# Hand.net
KiCad netlist of a schematic drawn in EAGLE
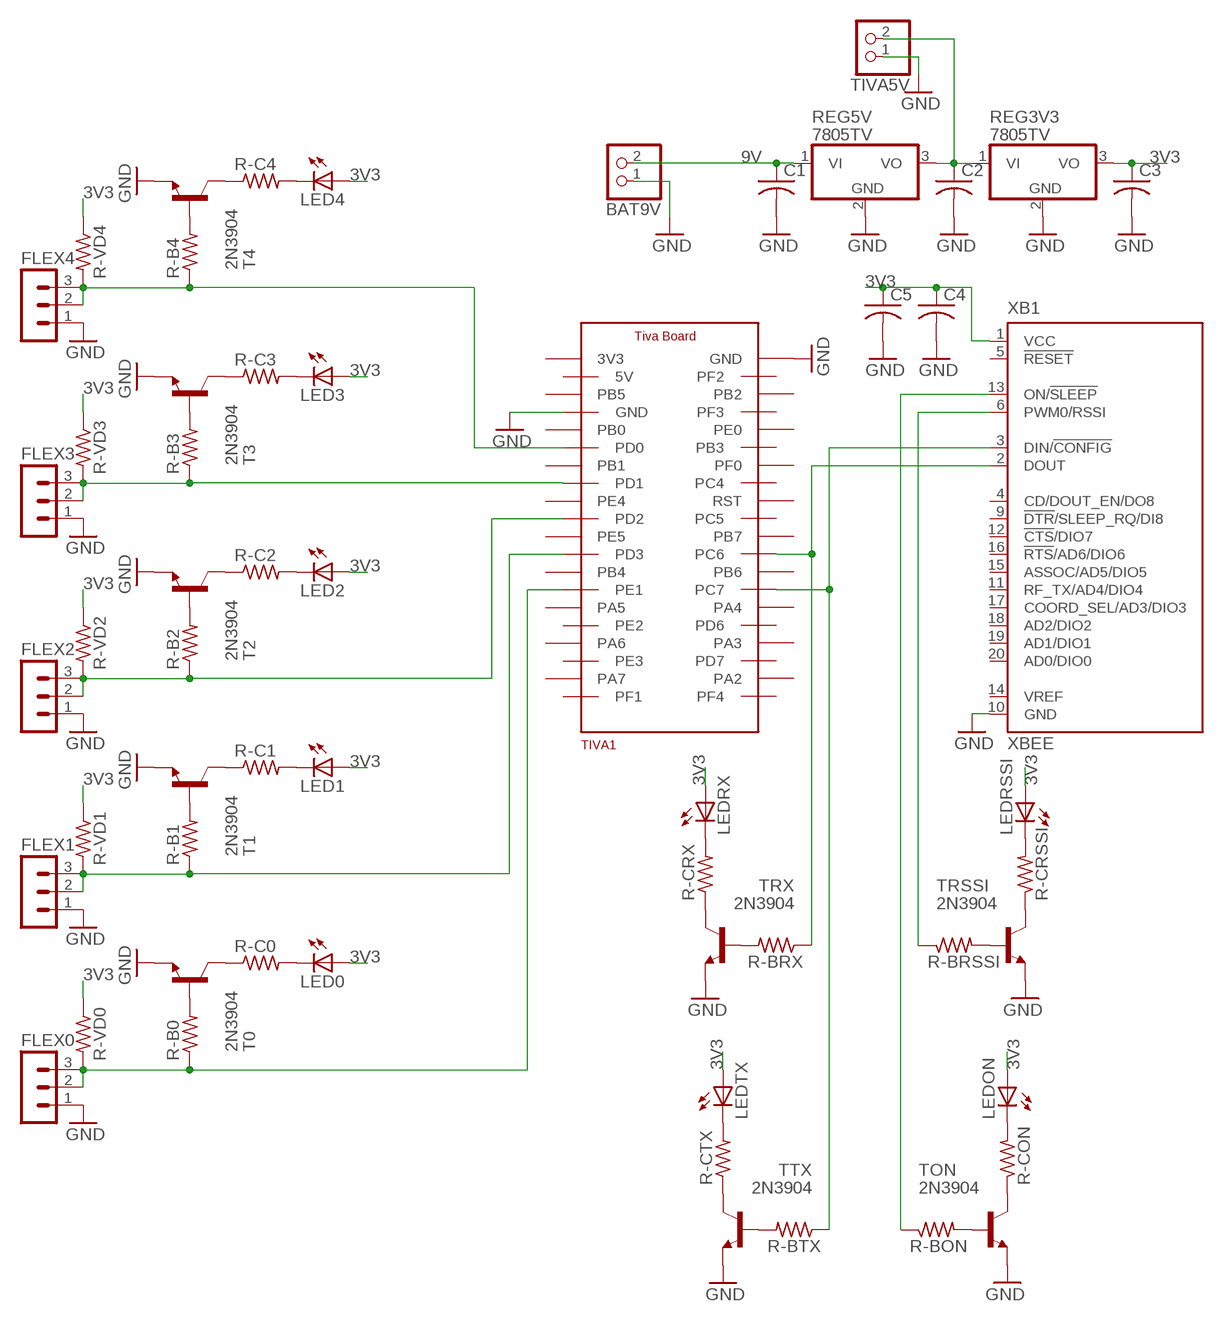
[diagram p0: schematic, sheet 1]

(export (version "E")
  (design (tool "Eeschema 10.0.6"))
  (components
    (comp (ref "BAT9V")
      (value "PINHD-1X2")
      (footprint "eagle-import:1X02")
      (libsource (lib "eagle-import") (part "PINHD-1X2"))
    )
    (comp (ref "C1")
      (value "C-US025-025X050")
      (footprint "eagle-import:C025-025X050")
      (libsource (lib "eagle-import") (part "C-US025-025X050"))
    )
    (comp (ref "C2")
      (value "C-US025-025X050")
      (footprint "eagle-import:C025-025X050")
      (libsource (lib "eagle-import") (part "C-US025-025X050"))
    )
    (comp (ref "C3")
      (value "C-US025-025X050")
      (footprint "eagle-import:C025-025X050")
      (libsource (lib "eagle-import") (part "C-US025-025X050"))
    )
    (comp (ref "C4")
      (value "C-US025-025X050")
      (footprint "eagle-import:C025-025X050")
      (libsource (lib "eagle-import") (part "C-US025-025X050"))
    )
    (comp (ref "C5")
      (value "C-US025-025X050")
      (footprint "eagle-import:C025-025X050")
      (libsource (lib "eagle-import") (part "C-US025-025X050"))
    )
    (comp (ref "FLEX0")
      (value "MA03-1")
      (footprint "eagle-import:MA03-1")
      (libsource (lib "eagle-import") (part "MA03-1"))
    )
    (comp (ref "FLEX1")
      (value "MA03-1")
      (footprint "eagle-import:MA03-1")
      (libsource (lib "eagle-import") (part "MA03-1"))
    )
    (comp (ref "FLEX2")
      (value "MA03-1")
      (footprint "eagle-import:MA03-1")
      (libsource (lib "eagle-import") (part "MA03-1"))
    )
    (comp (ref "FLEX3")
      (value "MA03-1")
      (footprint "eagle-import:MA03-1")
      (libsource (lib "eagle-import") (part "MA03-1"))
    )
    (comp (ref "FLEX4")
      (value "MA03-1")
      (footprint "eagle-import:MA03-1")
      (libsource (lib "eagle-import") (part "MA03-1"))
    )
    (comp (ref "LED0")
      (value "LED5MM")
      (footprint "eagle-import:LED5MM")
      (libsource (lib "eagle-import") (part "LED5MM"))
    )
    (comp (ref "LED1")
      (value "LED5MM")
      (footprint "eagle-import:LED5MM")
      (libsource (lib "eagle-import") (part "LED5MM"))
    )
    (comp (ref "LED2")
      (value "LED5MM")
      (footprint "eagle-import:LED5MM")
      (libsource (lib "eagle-import") (part "LED5MM"))
    )
    (comp (ref "LED3")
      (value "LED5MM")
      (footprint "eagle-import:LED5MM")
      (libsource (lib "eagle-import") (part "LED5MM"))
    )
    (comp (ref "LED4")
      (value "LED5MM")
      (footprint "eagle-import:LED5MM")
      (libsource (lib "eagle-import") (part "LED5MM"))
    )
    (comp (ref "LEDON")
      (value "LED5MM")
      (footprint "eagle-import:LED5MM")
      (libsource (lib "eagle-import") (part "LED5MM"))
    )
    (comp (ref "LEDRSSI")
      (value "LED5MM")
      (footprint "eagle-import:LED5MM")
      (libsource (lib "eagle-import") (part "LED5MM"))
    )
    (comp (ref "LEDRX")
      (value "LED5MM")
      (footprint "eagle-import:LED5MM")
      (libsource (lib "eagle-import") (part "LED5MM"))
    )
    (comp (ref "LEDTX")
      (value "LED5MM")
      (footprint "eagle-import:LED5MM")
      (libsource (lib "eagle-import") (part "LED5MM"))
    )
    (comp (ref "R-B0")
      (value "R-US_0204/7")
      (footprint "eagle-import:0204_7")
      (libsource (lib "eagle-import") (part "R-US_0204/7"))
    )
    (comp (ref "R-B1")
      (value "R-US_0204/7")
      (footprint "eagle-import:0204_7")
      (libsource (lib "eagle-import") (part "R-US_0204/7"))
    )
    (comp (ref "R-B2")
      (value "R-US_0204/7")
      (footprint "eagle-import:0204_7")
      (libsource (lib "eagle-import") (part "R-US_0204/7"))
    )
    (comp (ref "R-B3")
      (value "R-US_0204/7")
      (footprint "eagle-import:0204_7")
      (libsource (lib "eagle-import") (part "R-US_0204/7"))
    )
    (comp (ref "R-B4")
      (value "R-US_0204/7")
      (footprint "eagle-import:0204_7")
      (libsource (lib "eagle-import") (part "R-US_0204/7"))
    )
    (comp (ref "R-BON")
      (value "R-US_0204/7")
      (footprint "eagle-import:0204_7")
      (libsource (lib "eagle-import") (part "R-US_0204/7"))
    )
    (comp (ref "R-BRSSI")
      (value "R-US_0204/7")
      (footprint "eagle-import:0204_7")
      (libsource (lib "eagle-import") (part "R-US_0204/7"))
    )
    (comp (ref "R-BRX")
      (value "R-US_0204/7")
      (footprint "eagle-import:0204_7")
      (libsource (lib "eagle-import") (part "R-US_0204/7"))
    )
    (comp (ref "R-BTX")
      (value "R-US_0204/7")
      (footprint "eagle-import:0204_7")
      (libsource (lib "eagle-import") (part "R-US_0204/7"))
    )
    (comp (ref "R-C0")
      (value "R-US_0204/7")
      (footprint "eagle-import:0204_7")
      (libsource (lib "eagle-import") (part "R-US_0204/7"))
    )
    (comp (ref "R-C1")
      (value "R-US_0204/7")
      (footprint "eagle-import:0204_7")
      (libsource (lib "eagle-import") (part "R-US_0204/7"))
    )
    (comp (ref "R-C2")
      (value "R-US_0204/7")
      (footprint "eagle-import:0204_7")
      (libsource (lib "eagle-import") (part "R-US_0204/7"))
    )
    (comp (ref "R-C3")
      (value "R-US_0204/7")
      (footprint "eagle-import:0204_7")
      (libsource (lib "eagle-import") (part "R-US_0204/7"))
    )
    (comp (ref "R-C4")
      (value "R-US_0204/7")
      (footprint "eagle-import:0204_7")
      (libsource (lib "eagle-import") (part "R-US_0204/7"))
    )
    (comp (ref "R-CON")
      (value "R-US_0204/7")
      (footprint "eagle-import:0204_7")
      (libsource (lib "eagle-import") (part "R-US_0204/7"))
    )
    (comp (ref "R-CRSSI")
      (value "R-US_0204/7")
      (footprint "eagle-import:0204_7")
      (libsource (lib "eagle-import") (part "R-US_0204/7"))
    )
    (comp (ref "R-CRX")
      (value "R-US_0204/7")
      (footprint "eagle-import:0204_7")
      (libsource (lib "eagle-import") (part "R-US_0204/7"))
    )
    (comp (ref "R-CTX")
      (value "R-US_0204/7")
      (footprint "eagle-import:0204_7")
      (libsource (lib "eagle-import") (part "R-US_0204/7"))
    )
    (comp (ref "R-VD0")
      (value "R-US_0204/7")
      (footprint "eagle-import:0204_7")
      (libsource (lib "eagle-import") (part "R-US_0204/7"))
    )
    (comp (ref "R-VD1")
      (value "R-US_0204/7")
      (footprint "eagle-import:0204_7")
      (libsource (lib "eagle-import") (part "R-US_0204/7"))
    )
    (comp (ref "R-VD2")
      (value "R-US_0204/7")
      (footprint "eagle-import:0204_7")
      (libsource (lib "eagle-import") (part "R-US_0204/7"))
    )
    (comp (ref "R-VD3")
      (value "R-US_0204/7")
      (footprint "eagle-import:0204_7")
      (libsource (lib "eagle-import") (part "R-US_0204/7"))
    )
    (comp (ref "R-VD4")
      (value "R-US_0204/7")
      (footprint "eagle-import:0204_7")
      (libsource (lib "eagle-import") (part "R-US_0204/7"))
    )
    (comp (ref "REG3V3")
      (value "7805TV")
      (footprint "eagle-import:TO220V")
      (libsource (lib "eagle-import") (part "78TV05"))
    )
    (comp (ref "REG5V")
      (value "7805TV")
      (footprint "eagle-import:TO220V")
      (libsource (lib "eagle-import") (part "78TV05"))
    )
    (comp (ref "T0")
      (value "2N3904")
      (footprint "eagle-import:TO92")
      (libsource (lib "eagle-import") (part "2N3904"))
    )
    (comp (ref "T1")
      (value "2N3904")
      (footprint "eagle-import:TO92")
      (libsource (lib "eagle-import") (part "2N3904"))
    )
    (comp (ref "T2")
      (value "2N3904")
      (footprint "eagle-import:TO92")
      (libsource (lib "eagle-import") (part "2N3904"))
    )
    (comp (ref "T3")
      (value "2N3904")
      (footprint "eagle-import:TO92")
      (libsource (lib "eagle-import") (part "2N3904"))
    )
    (comp (ref "T4")
      (value "2N3904")
      (footprint "eagle-import:TO92")
      (libsource (lib "eagle-import") (part "2N3904"))
    )
    (comp (ref "TIVA1")
      (value "TIVA-BOARD")
      (footprint "eagle-import:TIVA-BOARD")
      (libsource (lib "eagle-import") (part "TIVA-BOARD"))
    )
    (comp (ref "TIVA5V")
      (value "PINHD-1X2")
      (footprint "eagle-import:1X02")
      (libsource (lib "eagle-import") (part "PINHD-1X2"))
    )
    (comp (ref "TON")
      (value "2N3904")
      (footprint "eagle-import:TO92")
      (libsource (lib "eagle-import") (part "2N3904"))
    )
    (comp (ref "TRSSI")
      (value "2N3904")
      (footprint "eagle-import:TO92")
      (libsource (lib "eagle-import") (part "2N3904"))
    )
    (comp (ref "TRX")
      (value "2N3904")
      (footprint "eagle-import:TO92")
      (libsource (lib "eagle-import") (part "2N3904"))
    )
    (comp (ref "TTX")
      (value "2N3904")
      (footprint "eagle-import:TO92")
      (libsource (lib "eagle-import") (part "2N3904"))
    )
    (comp (ref "XB1")
      (value "XBEE")
      (footprint "eagle-import:XBEE")
      (fields (field (name "MPN") "XBP24-Z7UIT-004"))
      (libsource (lib "eagle-import") (part "XBEE"))
    )
  )
  (nets
    (net (code "1") (name "/3V3") (class "Default")
      (node (ref "C3") (pin "1") (pinfunction "1_1") (pintype "passive"))
      (node (ref "C4") (pin "1") (pinfunction "1_1") (pintype "passive"))
      (node (ref "C5") (pin "1") (pinfunction "1_1") (pintype "passive"))
      (node (ref "LED0") (pin "A") (pinfunction "A_A") (pintype "passive"))
      (node (ref "LED1") (pin "A") (pinfunction "A_A") (pintype "passive"))
      (node (ref "LED2") (pin "A") (pinfunction "A_A") (pintype "passive"))
      (node (ref "LED3") (pin "A") (pinfunction "A_A") (pintype "passive"))
      (node (ref "LED4") (pin "A") (pinfunction "A_A") (pintype "passive"))
      (node (ref "LEDON") (pin "A") (pinfunction "A_A") (pintype "passive"))
      (node (ref "LEDRSSI") (pin "A") (pinfunction "A_A") (pintype "passive"))
      (node (ref "LEDRX") (pin "A") (pinfunction "A_A") (pintype "passive"))
      (node (ref "LEDTX") (pin "A") (pinfunction "A_A") (pintype "passive"))
      (node (ref "R-VD0") (pin "1") (pinfunction "1_1") (pintype "passive"))
      (node (ref "R-VD1") (pin "1") (pinfunction "1_1") (pintype "passive"))
      (node (ref "R-VD2") (pin "1") (pinfunction "1_1") (pintype "passive"))
      (node (ref "R-VD3") (pin "1") (pinfunction "1_1") (pintype "passive"))
      (node (ref "R-VD4") (pin "1") (pinfunction "1_1") (pintype "passive"))
      (node (ref "REG3V3") (pin "3") (pinfunction "VO_3") (pintype "passive"))
      (node (ref "XB1") (pin "1") (pinfunction "VCC_1") (pintype "power_in"))
    )
    (net (code "2") (name "/9V") (class "Default")
      (node (ref "BAT9V") (pin "2") (pinfunction "2_2") (pintype "passive"))
      (node (ref "C1") (pin "1") (pinfunction "1_1") (pintype "passive"))
      (node (ref "REG5V") (pin "1") (pinfunction "VI_1") (pintype "input"))
    )
    (net (code "3") (name "GND") (class "Default")
      (node (ref "BAT9V") (pin "1") (pinfunction "1_1") (pintype "passive"))
      (node (ref "C1") (pin "2") (pinfunction "2_2") (pintype "passive"))
      (node (ref "C2") (pin "2") (pinfunction "2_2") (pintype "passive"))
      (node (ref "C3") (pin "2") (pinfunction "2_2") (pintype "passive"))
      (node (ref "C4") (pin "2") (pinfunction "2_2") (pintype "passive"))
      (node (ref "C5") (pin "2") (pinfunction "2_2") (pintype "passive"))
      (node (ref "FLEX0") (pin "1") (pinfunction "1_1") (pintype "passive"))
      (node (ref "FLEX1") (pin "1") (pinfunction "1_1") (pintype "passive"))
      (node (ref "FLEX2") (pin "1") (pinfunction "1_1") (pintype "passive"))
      (node (ref "FLEX3") (pin "1") (pinfunction "1_1") (pintype "passive"))
      (node (ref "FLEX4") (pin "1") (pinfunction "1_1") (pintype "passive"))
      (node (ref "REG3V3") (pin "2") (pinfunction "GND_2") (pintype "passive"))
      (node (ref "REG5V") (pin "2") (pinfunction "GND_2") (pintype "passive"))
      (node (ref "T0") (pin "3") (pinfunction "E_3") (pintype "passive"))
      (node (ref "T1") (pin "3") (pinfunction "E_3") (pintype "passive"))
      (node (ref "T2") (pin "3") (pinfunction "E_3") (pintype "passive"))
      (node (ref "T3") (pin "3") (pinfunction "E_3") (pintype "passive"))
      (node (ref "T4") (pin "3") (pinfunction "E_3") (pintype "passive"))
      (node (ref "TIVA1") (pin "GND@1") (pinfunction "GND_GND@1") (pintype "bidirectional"))
      (node (ref "TIVA1") (pin "GND@2") (pinfunction "GND_GND@2") (pintype "bidirectional"))
      (node (ref "TIVA5V") (pin "1") (pinfunction "1_1") (pintype "passive"))
      (node (ref "TON") (pin "3") (pinfunction "E_3") (pintype "passive"))
      (node (ref "TRSSI") (pin "3") (pinfunction "E_3") (pintype "passive"))
      (node (ref "TRX") (pin "3") (pinfunction "E_3") (pintype "passive"))
      (node (ref "TTX") (pin "3") (pinfunction "E_3") (pintype "passive"))
      (node (ref "XB1") (pin "10") (pinfunction "GND_10") (pintype "power_in"))
    )
    (net (code "4") (name "Net-(FLEX0-Pad2)") (class "Default")
      (node (ref "FLEX0") (pin "2") (pinfunction "2_2") (pintype "passive"))
      (node (ref "FLEX0") (pin "3") (pinfunction "3_3") (pintype "passive"))
      (node (ref "R-B0") (pin "1") (pinfunction "1_1") (pintype "passive"))
      (node (ref "R-VD0") (pin "2") (pinfunction "2_2") (pintype "passive"))
      (node (ref "TIVA1") (pin "PE1") (pinfunction "PE1_PE1") (pintype "bidirectional"))
    )
    (net (code "5") (name "Net-(FLEX1-Pad2)") (class "Default")
      (node (ref "FLEX1") (pin "2") (pinfunction "2_2") (pintype "passive"))
      (node (ref "FLEX1") (pin "3") (pinfunction "3_3") (pintype "passive"))
      (node (ref "R-B1") (pin "1") (pinfunction "1_1") (pintype "passive"))
      (node (ref "R-VD1") (pin "2") (pinfunction "2_2") (pintype "passive"))
      (node (ref "TIVA1") (pin "PD3") (pinfunction "PD3_PD3") (pintype "bidirectional"))
    )
    (net (code "6") (name "Net-(FLEX2-Pad2)") (class "Default")
      (node (ref "FLEX2") (pin "2") (pinfunction "2_2") (pintype "passive"))
      (node (ref "FLEX2") (pin "3") (pinfunction "3_3") (pintype "passive"))
      (node (ref "R-B2") (pin "1") (pinfunction "1_1") (pintype "passive"))
      (node (ref "R-VD2") (pin "2") (pinfunction "2_2") (pintype "passive"))
      (node (ref "TIVA1") (pin "PD2") (pinfunction "PD2_PD2") (pintype "bidirectional"))
    )
    (net (code "7") (name "Net-(FLEX3-Pad2)") (class "Default")
      (node (ref "FLEX3") (pin "2") (pinfunction "2_2") (pintype "passive"))
      (node (ref "FLEX3") (pin "3") (pinfunction "3_3") (pintype "passive"))
      (node (ref "R-B3") (pin "1") (pinfunction "1_1") (pintype "passive"))
      (node (ref "R-VD3") (pin "2") (pinfunction "2_2") (pintype "passive"))
      (node (ref "TIVA1") (pin "PD1") (pinfunction "PD1_PD1") (pintype "bidirectional"))
    )
    (net (code "8") (name "Net-(FLEX4-Pad2)") (class "Default")
      (node (ref "FLEX4") (pin "2") (pinfunction "2_2") (pintype "passive"))
      (node (ref "FLEX4") (pin "3") (pinfunction "3_3") (pintype "passive"))
      (node (ref "R-B4") (pin "1") (pinfunction "1_1") (pintype "passive"))
      (node (ref "R-VD4") (pin "2") (pinfunction "2_2") (pintype "passive"))
      (node (ref "TIVA1") (pin "PD0") (pinfunction "PD0_PD0") (pintype "bidirectional"))
    )
    (net (code "9") (name "Net-(LED0-C)") (class "Default")
      (node (ref "LED0") (pin "K") (pinfunction "C_K") (pintype "passive"))
      (node (ref "R-C0") (pin "2") (pinfunction "2_2") (pintype "passive"))
    )
    (net (code "10") (name "Net-(LED1-C)") (class "Default")
      (node (ref "LED1") (pin "K") (pinfunction "C_K") (pintype "passive"))
      (node (ref "R-C1") (pin "2") (pinfunction "2_2") (pintype "passive"))
    )
    (net (code "11") (name "Net-(LED2-C)") (class "Default")
      (node (ref "LED2") (pin "K") (pinfunction "C_K") (pintype "passive"))
      (node (ref "R-C2") (pin "2") (pinfunction "2_2") (pintype "passive"))
    )
    (net (code "12") (name "Net-(LED3-C)") (class "Default")
      (node (ref "LED3") (pin "K") (pinfunction "C_K") (pintype "passive"))
      (node (ref "R-C3") (pin "2") (pinfunction "2_2") (pintype "passive"))
    )
    (net (code "13") (name "Net-(LED4-C)") (class "Default")
      (node (ref "LED4") (pin "K") (pinfunction "C_K") (pintype "passive"))
      (node (ref "R-C4") (pin "2") (pinfunction "2_2") (pintype "passive"))
    )
    (net (code "14") (name "Net-(LEDON-C)") (class "Default")
      (node (ref "LEDON") (pin "K") (pinfunction "C_K") (pintype "passive"))
      (node (ref "R-CON") (pin "2") (pinfunction "2_2") (pintype "passive"))
    )
    (net (code "15") (name "Net-(LEDRSSI-C)") (class "Default")
      (node (ref "LEDRSSI") (pin "K") (pinfunction "C_K") (pintype "passive"))
      (node (ref "R-CRSSI") (pin "2") (pinfunction "2_2") (pintype "passive"))
    )
    (net (code "16") (name "Net-(LEDRX-C)") (class "Default")
      (node (ref "LEDRX") (pin "K") (pinfunction "C_K") (pintype "passive"))
      (node (ref "R-CRX") (pin "2") (pinfunction "2_2") (pintype "passive"))
    )
    (net (code "17") (name "Net-(LEDTX-C)") (class "Default")
      (node (ref "LEDTX") (pin "K") (pinfunction "C_K") (pintype "passive"))
      (node (ref "R-CTX") (pin "2") (pinfunction "2_2") (pintype "passive"))
    )
    (net (code "18") (name "Net-(REG3V3-VI)") (class "Default")
      (node (ref "C2") (pin "1") (pinfunction "1_1") (pintype "passive"))
      (node (ref "REG3V3") (pin "1") (pinfunction "VI_1") (pintype "input"))
      (node (ref "REG5V") (pin "3") (pinfunction "VO_3") (pintype "passive"))
      (node (ref "TIVA5V") (pin "2") (pinfunction "2_2") (pintype "passive"))
    )
    (net (code "19") (name "Net-(T0-B)") (class "Default")
      (node (ref "R-B0") (pin "2") (pinfunction "2_2") (pintype "passive"))
      (node (ref "T0") (pin "2") (pinfunction "B_2") (pintype "passive"))
    )
    (net (code "20") (name "Net-(T0-C)") (class "Default")
      (node (ref "R-C0") (pin "1") (pinfunction "1_1") (pintype "passive"))
      (node (ref "T0") (pin "1") (pinfunction "C_1") (pintype "passive"))
    )
    (net (code "21") (name "Net-(T1-B)") (class "Default")
      (node (ref "R-B1") (pin "2") (pinfunction "2_2") (pintype "passive"))
      (node (ref "T1") (pin "2") (pinfunction "B_2") (pintype "passive"))
    )
    (net (code "22") (name "Net-(T1-C)") (class "Default")
      (node (ref "R-C1") (pin "1") (pinfunction "1_1") (pintype "passive"))
      (node (ref "T1") (pin "1") (pinfunction "C_1") (pintype "passive"))
    )
    (net (code "23") (name "Net-(T2-B)") (class "Default")
      (node (ref "R-B2") (pin "2") (pinfunction "2_2") (pintype "passive"))
      (node (ref "T2") (pin "2") (pinfunction "B_2") (pintype "passive"))
    )
    (net (code "24") (name "Net-(T2-C)") (class "Default")
      (node (ref "R-C2") (pin "1") (pinfunction "1_1") (pintype "passive"))
      (node (ref "T2") (pin "1") (pinfunction "C_1") (pintype "passive"))
    )
    (net (code "25") (name "Net-(T3-B)") (class "Default")
      (node (ref "R-B3") (pin "2") (pinfunction "2_2") (pintype "passive"))
      (node (ref "T3") (pin "2") (pinfunction "B_2") (pintype "passive"))
    )
    (net (code "26") (name "Net-(T3-C)") (class "Default")
      (node (ref "R-C3") (pin "1") (pinfunction "1_1") (pintype "passive"))
      (node (ref "T3") (pin "1") (pinfunction "C_1") (pintype "passive"))
    )
    (net (code "27") (name "Net-(T4-B)") (class "Default")
      (node (ref "R-B4") (pin "2") (pinfunction "2_2") (pintype "passive"))
      (node (ref "T4") (pin "2") (pinfunction "B_2") (pintype "passive"))
    )
    (net (code "28") (name "Net-(T4-C)") (class "Default")
      (node (ref "R-C4") (pin "1") (pinfunction "1_1") (pintype "passive"))
      (node (ref "T4") (pin "1") (pinfunction "C_1") (pintype "passive"))
    )
    (net (code "29") (name "Net-(TON-B)") (class "Default")
      (node (ref "R-BON") (pin "2") (pinfunction "2_2") (pintype "passive"))
      (node (ref "TON") (pin "2") (pinfunction "B_2") (pintype "passive"))
    )
    (net (code "30") (name "Net-(TON-C)") (class "Default")
      (node (ref "R-CON") (pin "1") (pinfunction "1_1") (pintype "passive"))
      (node (ref "TON") (pin "1") (pinfunction "C_1") (pintype "passive"))
    )
    (net (code "31") (name "Net-(TRSSI-B)") (class "Default")
      (node (ref "R-BRSSI") (pin "2") (pinfunction "2_2") (pintype "passive"))
      (node (ref "TRSSI") (pin "2") (pinfunction "B_2") (pintype "passive"))
    )
    (net (code "32") (name "Net-(TRSSI-C)") (class "Default")
      (node (ref "R-CRSSI") (pin "1") (pinfunction "1_1") (pintype "passive"))
      (node (ref "TRSSI") (pin "1") (pinfunction "C_1") (pintype "passive"))
    )
    (net (code "33") (name "Net-(TRX-B)") (class "Default")
      (node (ref "R-BRX") (pin "2") (pinfunction "2_2") (pintype "passive"))
      (node (ref "TRX") (pin "2") (pinfunction "B_2") (pintype "passive"))
    )
    (net (code "34") (name "Net-(TRX-C)") (class "Default")
      (node (ref "R-CRX") (pin "1") (pinfunction "1_1") (pintype "passive"))
      (node (ref "TRX") (pin "1") (pinfunction "C_1") (pintype "passive"))
    )
    (net (code "35") (name "Net-(TTX-B)") (class "Default")
      (node (ref "R-BTX") (pin "2") (pinfunction "2_2") (pintype "passive"))
      (node (ref "TTX") (pin "2") (pinfunction "B_2") (pintype "passive"))
    )
    (net (code "36") (name "Net-(TTX-C)") (class "Default")
      (node (ref "R-CTX") (pin "1") (pinfunction "1_1") (pintype "passive"))
      (node (ref "TTX") (pin "1") (pinfunction "C_1") (pintype "passive"))
    )
    (net (code "37") (name "Net-(XB1-DIN{slash}~{CONFIG})") (class "Default")
      (node (ref "R-BTX") (pin "1") (pinfunction "1_1") (pintype "passive"))
      (node (ref "TIVA1") (pin "PC7") (pinfunction "PC7_PC7") (pintype "bidirectional"))
      (node (ref "XB1") (pin "3") (pinfunction "DIN/~{CONFIG}_3") (pintype "input"))
    )
    (net (code "38") (name "Net-(XB1-DOUT)") (class "Default")
      (node (ref "R-BRX") (pin "1") (pinfunction "1_1") (pintype "passive"))
      (node (ref "TIVA1") (pin "PC6") (pinfunction "PC6_PC6") (pintype "bidirectional"))
      (node (ref "XB1") (pin "2") (pinfunction "DOUT_2") (pintype "output"))
    )
    (net (code "39") (name "Net-(XB1-ON{slash}~{SLEEP})") (class "Default")
      (node (ref "R-BON") (pin "1") (pinfunction "1_1") (pintype "passive"))
      (node (ref "XB1") (pin "13") (pinfunction "ON/~{SLEEP}_13") (pintype "output"))
    )
    (net (code "40") (name "Net-(XB1-PWM0{slash}RSSI)") (class "Default")
      (node (ref "R-BRSSI") (pin "1") (pinfunction "1_1") (pintype "passive"))
      (node (ref "XB1") (pin "6") (pinfunction "PWM0/RSSI_6") (pintype "output"))
    )
    (net (code "41") (name "unconnected-(TIVA1-3V3-Pad3.3V)") (class "Default")
      (node (ref "TIVA1") (pin "3.3V") (pinfunction "3V3_3.3V") (pintype "bidirectional"))
    )
    (net (code "42") (name "unconnected-(TIVA1-Pad5V)") (class "Default")
      (node (ref "TIVA1") (pin "5V") (pinfunction "5V_5V") (pintype "bidirectional"))
    )
    (net (code "43") (name "unconnected-(TIVA1-PadPA2)") (class "Default")
      (node (ref "TIVA1") (pin "PA2") (pinfunction "PA2_PA2") (pintype "bidirectional"))
    )
    (net (code "44") (name "unconnected-(TIVA1-PadPA3)") (class "Default")
      (node (ref "TIVA1") (pin "PA3") (pinfunction "PA3_PA3") (pintype "bidirectional"))
    )
    (net (code "45") (name "unconnected-(TIVA1-PadPA4)") (class "Default")
      (node (ref "TIVA1") (pin "PA4") (pinfunction "PA4_PA4") (pintype "bidirectional"))
    )
    (net (code "46") (name "unconnected-(TIVA1-PadPA5)") (class "Default")
      (node (ref "TIVA1") (pin "PA5") (pinfunction "PA5_PA5") (pintype "bidirectional"))
    )
    (net (code "47") (name "unconnected-(TIVA1-PadPA6)") (class "Default")
      (node (ref "TIVA1") (pin "PA6") (pinfunction "PA6_PA6") (pintype "bidirectional"))
    )
    (net (code "48") (name "unconnected-(TIVA1-PadPA7)") (class "Default")
      (node (ref "TIVA1") (pin "PA7") (pinfunction "PA7_PA7") (pintype "bidirectional"))
    )
    (net (code "49") (name "unconnected-(TIVA1-PadPB0)") (class "Default")
      (node (ref "TIVA1") (pin "PB0") (pinfunction "PB0_PB0") (pintype "bidirectional"))
    )
    (net (code "50") (name "unconnected-(TIVA1-PadPB1)") (class "Default")
      (node (ref "TIVA1") (pin "PB1") (pinfunction "PB1_PB1") (pintype "bidirectional"))
    )
    (net (code "51") (name "unconnected-(TIVA1-PadPB2)") (class "Default")
      (node (ref "TIVA1") (pin "PB2") (pinfunction "PB2_PB2") (pintype "bidirectional"))
    )
    (net (code "52") (name "unconnected-(TIVA1-PadPB3)") (class "Default")
      (node (ref "TIVA1") (pin "PB3") (pinfunction "PB3_PB3") (pintype "bidirectional"))
    )
    (net (code "53") (name "unconnected-(TIVA1-PadPB4)") (class "Default")
      (node (ref "TIVA1") (pin "PB4") (pinfunction "PB4_PB4") (pintype "bidirectional"))
    )
    (net (code "54") (name "unconnected-(TIVA1-PadPB5)") (class "Default")
      (node (ref "TIVA1") (pin "PB5") (pinfunction "PB5_PB5") (pintype "bidirectional"))
    )
    (net (code "55") (name "unconnected-(TIVA1-PadPB6)") (class "Default")
      (node (ref "TIVA1") (pin "PB6") (pinfunction "PB6_PB6") (pintype "bidirectional"))
    )
    (net (code "56") (name "unconnected-(TIVA1-PadPB7)") (class "Default")
      (node (ref "TIVA1") (pin "PB7") (pinfunction "PB7_PB7") (pintype "bidirectional"))
    )
    (net (code "57") (name "unconnected-(TIVA1-PadPC4)") (class "Default")
      (node (ref "TIVA1") (pin "PC4") (pinfunction "PC4_PC4") (pintype "bidirectional"))
    )
    (net (code "58") (name "unconnected-(TIVA1-PadPC5)") (class "Default")
      (node (ref "TIVA1") (pin "PC5") (pinfunction "PC5_PC5") (pintype "bidirectional"))
    )
    (net (code "59") (name "unconnected-(TIVA1-PadPD6)") (class "Default")
      (node (ref "TIVA1") (pin "PD6") (pinfunction "PD6_PD6") (pintype "bidirectional"))
    )
    (net (code "60") (name "unconnected-(TIVA1-PadPD7)") (class "Default")
      (node (ref "TIVA1") (pin "PD7") (pinfunction "PD7_PD7") (pintype "bidirectional"))
    )
    (net (code "61") (name "unconnected-(TIVA1-PadPE0)") (class "Default")
      (node (ref "TIVA1") (pin "PE0") (pinfunction "PE0_PE0") (pintype "bidirectional"))
    )
    (net (code "62") (name "unconnected-(TIVA1-PadPE2)") (class "Default")
      (node (ref "TIVA1") (pin "PE2") (pinfunction "PE2_PE2") (pintype "bidirectional"))
    )
    (net (code "63") (name "unconnected-(TIVA1-PadPE3)") (class "Default")
      (node (ref "TIVA1") (pin "PE3") (pinfunction "PE3_PE3") (pintype "bidirectional"))
    )
    (net (code "64") (name "unconnected-(TIVA1-PadPE4)") (class "Default")
      (node (ref "TIVA1") (pin "PE4") (pinfunction "PE4_PE4") (pintype "bidirectional"))
    )
    (net (code "65") (name "unconnected-(TIVA1-PadPE5)") (class "Default")
      (node (ref "TIVA1") (pin "PE5") (pinfunction "PE5_PE5") (pintype "bidirectional"))
    )
    (net (code "66") (name "unconnected-(TIVA1-PadPF0)") (class "Default")
      (node (ref "TIVA1") (pin "PF0") (pinfunction "PF0_PF0") (pintype "bidirectional"))
    )
    (net (code "67") (name "unconnected-(TIVA1-PadPF1)") (class "Default")
      (node (ref "TIVA1") (pin "PF1") (pinfunction "PF1_PF1") (pintype "bidirectional"))
    )
    (net (code "68") (name "unconnected-(TIVA1-PadPF2)") (class "Default")
      (node (ref "TIVA1") (pin "PF2") (pinfunction "PF2_PF2") (pintype "bidirectional"))
    )
    (net (code "69") (name "unconnected-(TIVA1-PadPF3)") (class "Default")
      (node (ref "TIVA1") (pin "PF3") (pinfunction "PF3_PF3") (pintype "bidirectional"))
    )
    (net (code "70") (name "unconnected-(TIVA1-PadPF4)") (class "Default")
      (node (ref "TIVA1") (pin "PF4") (pinfunction "PF4_PF4") (pintype "bidirectional"))
    )
    (net (code "71") (name "unconnected-(TIVA1-PadRST)") (class "Default")
      (node (ref "TIVA1") (pin "RST") (pinfunction "RST_RST") (pintype "bidirectional"))
    )
    (net (code "72") (name "unconnected-(XB1-AD0{slash}DIO0-Pad20)") (class "Default")
      (node (ref "XB1") (pin "20") (pinfunction "AD0/DIO0_20") (pintype "bidirectional"))
    )
    (net (code "73") (name "unconnected-(XB1-AD1{slash}DIO1-Pad19)") (class "Default")
      (node (ref "XB1") (pin "19") (pinfunction "AD1/DIO1_19") (pintype "bidirectional"))
    )
    (net (code "74") (name "unconnected-(XB1-AD2{slash}DIO2-Pad18)") (class "Default")
      (node (ref "XB1") (pin "18") (pinfunction "AD2/DIO2_18") (pintype "bidirectional"))
    )
    (net (code "75") (name "unconnected-(XB1-ASSOC{slash}AD5{slash}DIO5-Pad15)") (class "Default")
      (node (ref "XB1") (pin "15") (pinfunction "ASSOC/AD5/DIO5_15") (pintype "bidirectional"))
    )
    (net (code "76") (name "unconnected-(XB1-CD{slash}DOUT_EN{slash}DO8-Pad4)") (class "Default")
      (node (ref "XB1") (pin "4") (pinfunction "CD/DOUT_EN/DO8_4") (pintype "output"))
    )
    (net (code "77") (name "unconnected-(XB1-COORD_SEL{slash}AD3{slash}DIO3-Pad17)") (class "Default")
      (node (ref "XB1") (pin "17") (pinfunction "COORD_SEL/AD3/DIO3_17") (pintype "bidirectional"))
    )
    (net (code "78") (name "unconnected-(XB1-RF_TX{slash}AD4{slash}DIO4-Pad11)") (class "Default")
      (node (ref "XB1") (pin "11") (pinfunction "RF_TX/AD4/DIO4_11") (pintype "bidirectional"))
    )
    (net (code "79") (name "unconnected-(XB1-VREF-Pad14)") (class "Default")
      (node (ref "XB1") (pin "14") (pinfunction "VREF_14") (pintype "input"))
    )
    (net (code "80") (name "unconnected-(XB1-~{CTS}{slash}DIO7-Pad12)") (class "Default")
      (node (ref "XB1") (pin "12") (pinfunction "~{CTS}/DIO7_12") (pintype "bidirectional"))
    )
    (net (code "81") (name "unconnected-(XB1-~{DTR}{slash}SLEEP_RQ{slash}DI8-Pad9)") (class "Default")
      (node (ref "XB1") (pin "9") (pinfunction "~{DTR}/SLEEP_RQ/DI8_9") (pintype "bidirectional"))
    )
    (net (code "82") (name "unconnected-(XB1-~{RESET}-Pad5)") (class "Default")
      (node (ref "XB1") (pin "5") (pinfunction "~{RESET}_5") (pintype "input"))
    )
    (net (code "83") (name "unconnected-(XB1-~{RTS}{slash}AD6{slash}DIO6-Pad16)") (class "Default")
      (node (ref "XB1") (pin "16") (pinfunction "~{RTS}/AD6/DIO6_16") (pintype "bidirectional"))
    )
  )
)
